# Combine2Cards.net
KiCad netlist of a schematic drawn in EAGLE
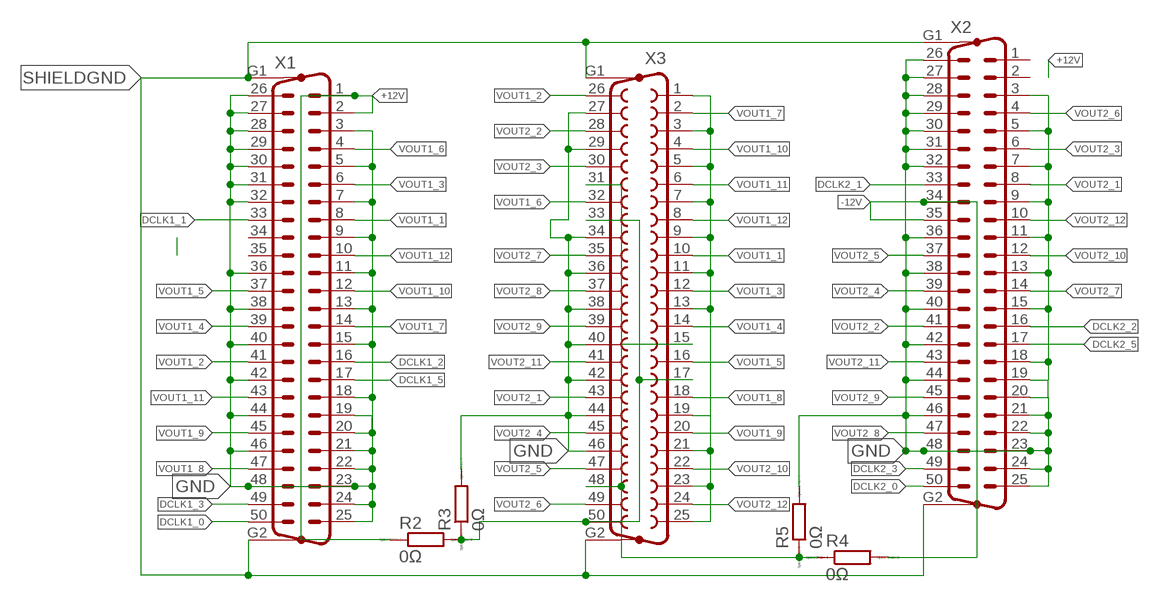
[diagram p0: schematic, sheet 1]

(export (version "E")
  (design (tool "Eeschema 10.0.6"))
  (components
    (comp (ref "R2")
      (value "0Ω")
      (footprint "eagle-import:R0603")
      (libsource (lib "eagle-import") (part "RR0603"))
    )
    (comp (ref "R3")
      (value "0Ω")
      (footprint "eagle-import:R0603")
      (libsource (lib "eagle-import") (part "RR0603"))
    )
    (comp (ref "R4")
      (value "0Ω")
      (footprint "eagle-import:R0603")
      (libsource (lib "eagle-import") (part "RR0603"))
    )
    (comp (ref "R5")
      (value "0Ω")
      (footprint "eagle-import:R0603")
      (libsource (lib "eagle-import") (part "RR0603"))
    )
    (comp (ref "X1")
      (value "M50VP")
      (footprint "eagle-import:M50VP")
      (libsource (lib "eagle-import") (part "M50VP"))
    )
    (comp (ref "X2")
      (value "M50VP")
      (footprint "eagle-import:M50VP")
      (libsource (lib "eagle-import") (part "M50VP"))
    )
    (comp (ref "X3")
      (value "F50VP")
      (footprint "eagle-import:F50VP")
      (libsource (lib "eagle-import") (part "F50VP"))
    )
  )
  (nets
    (net (code "1") (name "+12V") (class "Default")
      (node (ref "R2") (pin "1") (pinfunction "1_1") (pintype "passive"))
      (node (ref "X1") (pin "1") (pinfunction "1_1") (pintype "passive"))
      (node (ref "X1") (pin "2") (pinfunction "2_2") (pintype "passive"))
    )
    (net (code "2") (name "-12V") (class "Default")
      (node (ref "R4") (pin "2") (pinfunction "2_2") (pintype "passive"))
      (node (ref "X2") (pin "34") (pinfunction "34_34") (pintype "passive"))
      (node (ref "X2") (pin "35") (pinfunction "35_35") (pintype "passive"))
    )
    (net (code "3") (name "DCLK1_0") (class "Default")
      (node (ref "X1") (pin "50") (pinfunction "50_50") (pintype "passive"))
    )
    (net (code "4") (name "DCLK1_1") (class "Default")
      (node (ref "X1") (pin "33") (pinfunction "33_33") (pintype "passive"))
    )
    (net (code "5") (name "DCLK1_2") (class "Default")
      (node (ref "X1") (pin "16") (pinfunction "16_16") (pintype "passive"))
    )
    (net (code "6") (name "DCLK1_3") (class "Default")
      (node (ref "X1") (pin "49") (pinfunction "49_49") (pintype "passive"))
    )
    (net (code "7") (name "DCLK1_5") (class "Default")
      (node (ref "X1") (pin "17") (pinfunction "17_17") (pintype "passive"))
    )
    (net (code "8") (name "DCLK2_0") (class "Default")
      (node (ref "X2") (pin "50") (pinfunction "50_50") (pintype "passive"))
    )
    (net (code "9") (name "DCLK2_1") (class "Default")
      (node (ref "X2") (pin "33") (pinfunction "33_33") (pintype "passive"))
    )
    (net (code "10") (name "DCLK2_2") (class "Default")
      (node (ref "X2") (pin "16") (pinfunction "16_16") (pintype "passive"))
    )
    (net (code "11") (name "DCLK2_3") (class "Default")
      (node (ref "X2") (pin "49") (pinfunction "49_49") (pintype "passive"))
    )
    (net (code "12") (name "DCLK2_5") (class "Default")
      (node (ref "X2") (pin "17") (pinfunction "17_17") (pintype "passive"))
    )
    (net (code "13") (name "GND") (class "Default")
      (node (ref "R3") (pin "2") (pinfunction "2_2") (pintype "passive"))
      (node (ref "R5") (pin "2") (pinfunction "2_2") (pintype "passive"))
      (node (ref "X1") (pin "11") (pinfunction "11_11") (pintype "passive"))
      (node (ref "X1") (pin "13") (pinfunction "13_13") (pintype "passive"))
      (node (ref "X1") (pin "15") (pinfunction "15_15") (pintype "passive"))
      (node (ref "X1") (pin "18") (pinfunction "18_18") (pintype "passive"))
      (node (ref "X1") (pin "19") (pinfunction "19_19") (pintype "passive"))
      (node (ref "X1") (pin "20") (pinfunction "20_20") (pintype "passive"))
      (node (ref "X1") (pin "21") (pinfunction "21_21") (pintype "passive"))
      (node (ref "X1") (pin "22") (pinfunction "22_22") (pintype "passive"))
      (node (ref "X1") (pin "23") (pinfunction "23_23") (pintype "passive"))
      (node (ref "X1") (pin "24") (pinfunction "24_24") (pintype "passive"))
      (node (ref "X1") (pin "25") (pinfunction "25_25") (pintype "passive"))
      (node (ref "X1") (pin "26") (pinfunction "26_26") (pintype "passive"))
      (node (ref "X1") (pin "27") (pinfunction "27_27") (pintype "passive"))
      (node (ref "X1") (pin "28") (pinfunction "28_28") (pintype "passive"))
      (node (ref "X1") (pin "29") (pinfunction "29_29") (pintype "passive"))
      (node (ref "X1") (pin "3") (pinfunction "3_3") (pintype "passive"))
      (node (ref "X1") (pin "30") (pinfunction "30_30") (pintype "passive"))
      (node (ref "X1") (pin "31") (pinfunction "31_31") (pintype "passive"))
      (node (ref "X1") (pin "32") (pinfunction "32_32") (pintype "passive"))
      (node (ref "X1") (pin "36") (pinfunction "36_36") (pintype "passive"))
      (node (ref "X1") (pin "38") (pinfunction "38_38") (pintype "passive"))
      (node (ref "X1") (pin "40") (pinfunction "40_40") (pintype "passive"))
      (node (ref "X1") (pin "42") (pinfunction "42_42") (pintype "passive"))
      (node (ref "X1") (pin "44") (pinfunction "44_44") (pintype "passive"))
      (node (ref "X1") (pin "46") (pinfunction "46_46") (pintype "passive"))
      (node (ref "X1") (pin "48") (pinfunction "48_48") (pintype "passive"))
      (node (ref "X1") (pin "5") (pinfunction "5_5") (pintype "passive"))
      (node (ref "X1") (pin "7") (pinfunction "7_7") (pintype "passive"))
      (node (ref "X1") (pin "9") (pinfunction "9_9") (pintype "passive"))
      (node (ref "X2") (pin "11") (pinfunction "11_11") (pintype "passive"))
      (node (ref "X2") (pin "13") (pinfunction "13_13") (pintype "passive"))
      (node (ref "X2") (pin "15") (pinfunction "15_15") (pintype "passive"))
      (node (ref "X2") (pin "18") (pinfunction "18_18") (pintype "passive"))
      (node (ref "X2") (pin "19") (pinfunction "19_19") (pintype "passive"))
      (node (ref "X2") (pin "20") (pinfunction "20_20") (pintype "passive"))
      (node (ref "X2") (pin "21") (pinfunction "21_21") (pintype "passive"))
      (node (ref "X2") (pin "22") (pinfunction "22_22") (pintype "passive"))
      (node (ref "X2") (pin "23") (pinfunction "23_23") (pintype "passive"))
      (node (ref "X2") (pin "24") (pinfunction "24_24") (pintype "passive"))
      (node (ref "X2") (pin "25") (pinfunction "25_25") (pintype "passive"))
      (node (ref "X2") (pin "26") (pinfunction "26_26") (pintype "passive"))
      (node (ref "X2") (pin "27") (pinfunction "27_27") (pintype "passive"))
      (node (ref "X2") (pin "28") (pinfunction "28_28") (pintype "passive"))
      (node (ref "X2") (pin "29") (pinfunction "29_29") (pintype "passive"))
      (node (ref "X2") (pin "3") (pinfunction "3_3") (pintype "passive"))
      (node (ref "X2") (pin "30") (pinfunction "30_30") (pintype "passive"))
      (node (ref "X2") (pin "31") (pinfunction "31_31") (pintype "passive"))
      (node (ref "X2") (pin "32") (pinfunction "32_32") (pintype "passive"))
      (node (ref "X2") (pin "36") (pinfunction "36_36") (pintype "passive"))
      (node (ref "X2") (pin "38") (pinfunction "38_38") (pintype "passive"))
      (node (ref "X2") (pin "40") (pinfunction "40_40") (pintype "passive"))
      (node (ref "X2") (pin "42") (pinfunction "42_42") (pintype "passive"))
      (node (ref "X2") (pin "44") (pinfunction "44_44") (pintype "passive"))
      (node (ref "X2") (pin "46") (pinfunction "46_46") (pintype "passive"))
      (node (ref "X2") (pin "48") (pinfunction "48_48") (pintype "passive"))
      (node (ref "X2") (pin "5") (pinfunction "5_5") (pintype "passive"))
      (node (ref "X2") (pin "7") (pinfunction "7_7") (pintype "passive"))
      (node (ref "X2") (pin "9") (pinfunction "9_9") (pintype "passive"))
      (node (ref "X3") (pin "1") (pinfunction "1_1") (pintype "passive"))
      (node (ref "X3") (pin "11") (pinfunction "11_11") (pintype "passive"))
      (node (ref "X3") (pin "13") (pinfunction "13_13") (pintype "passive"))
      (node (ref "X3") (pin "19") (pinfunction "19_19") (pintype "passive"))
      (node (ref "X3") (pin "21") (pinfunction "21_21") (pintype "passive"))
      (node (ref "X3") (pin "23") (pinfunction "23_23") (pintype "passive"))
      (node (ref "X3") (pin "25") (pinfunction "25_25") (pintype "passive"))
      (node (ref "X3") (pin "27") (pinfunction "27_27") (pintype "passive"))
      (node (ref "X3") (pin "29") (pinfunction "29_29") (pintype "passive"))
      (node (ref "X3") (pin "3") (pinfunction "3_3") (pintype "passive"))
      (node (ref "X3") (pin "34") (pinfunction "34_34") (pintype "passive"))
      (node (ref "X3") (pin "36") (pinfunction "36_36") (pintype "passive"))
      (node (ref "X3") (pin "38") (pinfunction "38_38") (pintype "passive"))
      (node (ref "X3") (pin "40") (pinfunction "40_40") (pintype "passive"))
      (node (ref "X3") (pin "42") (pinfunction "42_42") (pintype "passive"))
      (node (ref "X3") (pin "44") (pinfunction "44_44") (pintype "passive"))
      (node (ref "X3") (pin "46") (pinfunction "46_46") (pintype "passive"))
      (node (ref "X3") (pin "5") (pinfunction "5_5") (pintype "passive"))
      (node (ref "X3") (pin "7") (pinfunction "7_7") (pintype "passive"))
      (node (ref "X3") (pin "9") (pinfunction "9_9") (pintype "passive"))
    )
    (net (code "14") (name "Net-(R2-Pad2)") (class "Default")
      (node (ref "R2") (pin "2") (pinfunction "2_2") (pintype "passive"))
      (node (ref "R3") (pin "1") (pinfunction "1_1") (pintype "passive"))
      (node (ref "X3") (pin "17") (pinfunction "17_17") (pintype "passive"))
      (node (ref "X3") (pin "33") (pinfunction "33_33") (pintype "passive"))
      (node (ref "X3") (pin "50") (pinfunction "50_50") (pintype "passive"))
    )
    (net (code "15") (name "Net-(R4-Pad1)") (class "Default")
      (node (ref "R4") (pin "1") (pinfunction "1_1") (pintype "passive"))
      (node (ref "R5") (pin "1") (pinfunction "1_1") (pintype "passive"))
      (node (ref "X3") (pin "15") (pinfunction "15_15") (pintype "passive"))
      (node (ref "X3") (pin "31") (pinfunction "31_31") (pintype "passive"))
      (node (ref "X3") (pin "48") (pinfunction "48_48") (pintype "passive"))
    )
    (net (code "16") (name "SHIELDGND") (class "Default")
      (node (ref "X1") (pin "G1") (pinfunction "G1_G1") (pintype "passive"))
      (node (ref "X1") (pin "G2") (pinfunction "G2_G2") (pintype "passive"))
      (node (ref "X2") (pin "G1") (pinfunction "G1_G1") (pintype "passive"))
      (node (ref "X2") (pin "G2") (pinfunction "G2_G2") (pintype "passive"))
      (node (ref "X3") (pin "G1") (pinfunction "G1_G1") (pintype "passive"))
      (node (ref "X3") (pin "G2") (pinfunction "G2_G2") (pintype "passive"))
    )
    (net (code "17") (name "VOUT1_1") (class "Default")
      (node (ref "X1") (pin "8") (pinfunction "8_8") (pintype "passive"))
      (node (ref "X3") (pin "10") (pinfunction "10_10") (pintype "passive"))
    )
    (net (code "18") (name "VOUT1_2") (class "Default")
      (node (ref "X1") (pin "41") (pinfunction "41_41") (pintype "passive"))
      (node (ref "X3") (pin "26") (pinfunction "26_26") (pintype "passive"))
    )
    (net (code "19") (name "VOUT1_3") (class "Default")
      (node (ref "X1") (pin "6") (pinfunction "6_6") (pintype "passive"))
      (node (ref "X3") (pin "12") (pinfunction "12_12") (pintype "passive"))
    )
    (net (code "20") (name "VOUT1_4") (class "Default")
      (node (ref "X1") (pin "39") (pinfunction "39_39") (pintype "passive"))
      (node (ref "X3") (pin "14") (pinfunction "14_14") (pintype "passive"))
    )
    (net (code "21") (name "VOUT1_5") (class "Default")
      (node (ref "X1") (pin "37") (pinfunction "37_37") (pintype "passive"))
      (node (ref "X3") (pin "16") (pinfunction "16_16") (pintype "passive"))
    )
    (net (code "22") (name "VOUT1_6") (class "Default")
      (node (ref "X1") (pin "4") (pinfunction "4_4") (pintype "passive"))
      (node (ref "X3") (pin "32") (pinfunction "32_32") (pintype "passive"))
    )
    (net (code "23") (name "VOUT1_7") (class "Default")
      (node (ref "X1") (pin "14") (pinfunction "14_14") (pintype "passive"))
      (node (ref "X3") (pin "2") (pinfunction "2_2") (pintype "passive"))
    )
    (net (code "24") (name "VOUT1_8") (class "Default")
      (node (ref "X1") (pin "47") (pinfunction "47_47") (pintype "passive"))
      (node (ref "X3") (pin "18") (pinfunction "18_18") (pintype "passive"))
    )
    (net (code "25") (name "VOUT1_9") (class "Default")
      (node (ref "X1") (pin "45") (pinfunction "45_45") (pintype "passive"))
      (node (ref "X3") (pin "20") (pinfunction "20_20") (pintype "passive"))
    )
    (net (code "26") (name "VOUT1_10") (class "Default")
      (node (ref "X1") (pin "12") (pinfunction "12_12") (pintype "passive"))
      (node (ref "X3") (pin "4") (pinfunction "4_4") (pintype "passive"))
    )
    (net (code "27") (name "VOUT1_11") (class "Default")
      (node (ref "X1") (pin "43") (pinfunction "43_43") (pintype "passive"))
      (node (ref "X3") (pin "6") (pinfunction "6_6") (pintype "passive"))
    )
    (net (code "28") (name "VOUT1_12") (class "Default")
      (node (ref "X1") (pin "10") (pinfunction "10_10") (pintype "passive"))
      (node (ref "X3") (pin "8") (pinfunction "8_8") (pintype "passive"))
    )
    (net (code "29") (name "VOUT2_1") (class "Default")
      (node (ref "X2") (pin "8") (pinfunction "8_8") (pintype "passive"))
      (node (ref "X3") (pin "43") (pinfunction "43_43") (pintype "passive"))
    )
    (net (code "30") (name "VOUT2_2") (class "Default")
      (node (ref "X2") (pin "41") (pinfunction "41_41") (pintype "passive"))
      (node (ref "X3") (pin "28") (pinfunction "28_28") (pintype "passive"))
    )
    (net (code "31") (name "VOUT2_3") (class "Default")
      (node (ref "X2") (pin "6") (pinfunction "6_6") (pintype "passive"))
      (node (ref "X3") (pin "30") (pinfunction "30_30") (pintype "passive"))
    )
    (net (code "32") (name "VOUT2_4") (class "Default")
      (node (ref "X2") (pin "39") (pinfunction "39_39") (pintype "passive"))
      (node (ref "X3") (pin "45") (pinfunction "45_45") (pintype "passive"))
    )
    (net (code "33") (name "VOUT2_5") (class "Default")
      (node (ref "X2") (pin "37") (pinfunction "37_37") (pintype "passive"))
      (node (ref "X3") (pin "47") (pinfunction "47_47") (pintype "passive"))
    )
    (net (code "34") (name "VOUT2_6") (class "Default")
      (node (ref "X2") (pin "4") (pinfunction "4_4") (pintype "passive"))
      (node (ref "X3") (pin "49") (pinfunction "49_49") (pintype "passive"))
    )
    (net (code "35") (name "VOUT2_7") (class "Default")
      (node (ref "X2") (pin "14") (pinfunction "14_14") (pintype "passive"))
      (node (ref "X3") (pin "35") (pinfunction "35_35") (pintype "passive"))
    )
    (net (code "36") (name "VOUT2_8") (class "Default")
      (node (ref "X2") (pin "47") (pinfunction "47_47") (pintype "passive"))
      (node (ref "X3") (pin "37") (pinfunction "37_37") (pintype "passive"))
    )
    (net (code "37") (name "VOUT2_9") (class "Default")
      (node (ref "X2") (pin "45") (pinfunction "45_45") (pintype "passive"))
      (node (ref "X3") (pin "39") (pinfunction "39_39") (pintype "passive"))
    )
    (net (code "38") (name "VOUT2_10") (class "Default")
      (node (ref "X2") (pin "12") (pinfunction "12_12") (pintype "passive"))
      (node (ref "X3") (pin "22") (pinfunction "22_22") (pintype "passive"))
    )
    (net (code "39") (name "VOUT2_11") (class "Default")
      (node (ref "X2") (pin "43") (pinfunction "43_43") (pintype "passive"))
      (node (ref "X3") (pin "41") (pinfunction "41_41") (pintype "passive"))
    )
    (net (code "40") (name "VOUT2_12") (class "Default")
      (node (ref "X2") (pin "10") (pinfunction "10_10") (pintype "passive"))
      (node (ref "X3") (pin "24") (pinfunction "24_24") (pintype "passive"))
    )
    (net (code "41") (name "unconnected-(X1-Pad34)") (class "Default")
      (node (ref "X1") (pin "34") (pinfunction "34_34") (pintype "passive"))
    )
    (net (code "42") (name "unconnected-(X1-Pad35)") (class "Default")
      (node (ref "X1") (pin "35") (pinfunction "35_35") (pintype "passive"))
    )
    (net (code "43") (name "unconnected-(X2-Pad1)") (class "Default")
      (node (ref "X2") (pin "1") (pinfunction "1_1") (pintype "passive"))
    )
    (net (code "44") (name "unconnected-(X2-Pad2)") (class "Default")
      (node (ref "X2") (pin "2") (pinfunction "2_2") (pintype "passive"))
    )
  )
)
